# Adafruit_MMA8451.net
KiCad netlist of a schematic drawn in EAGLE
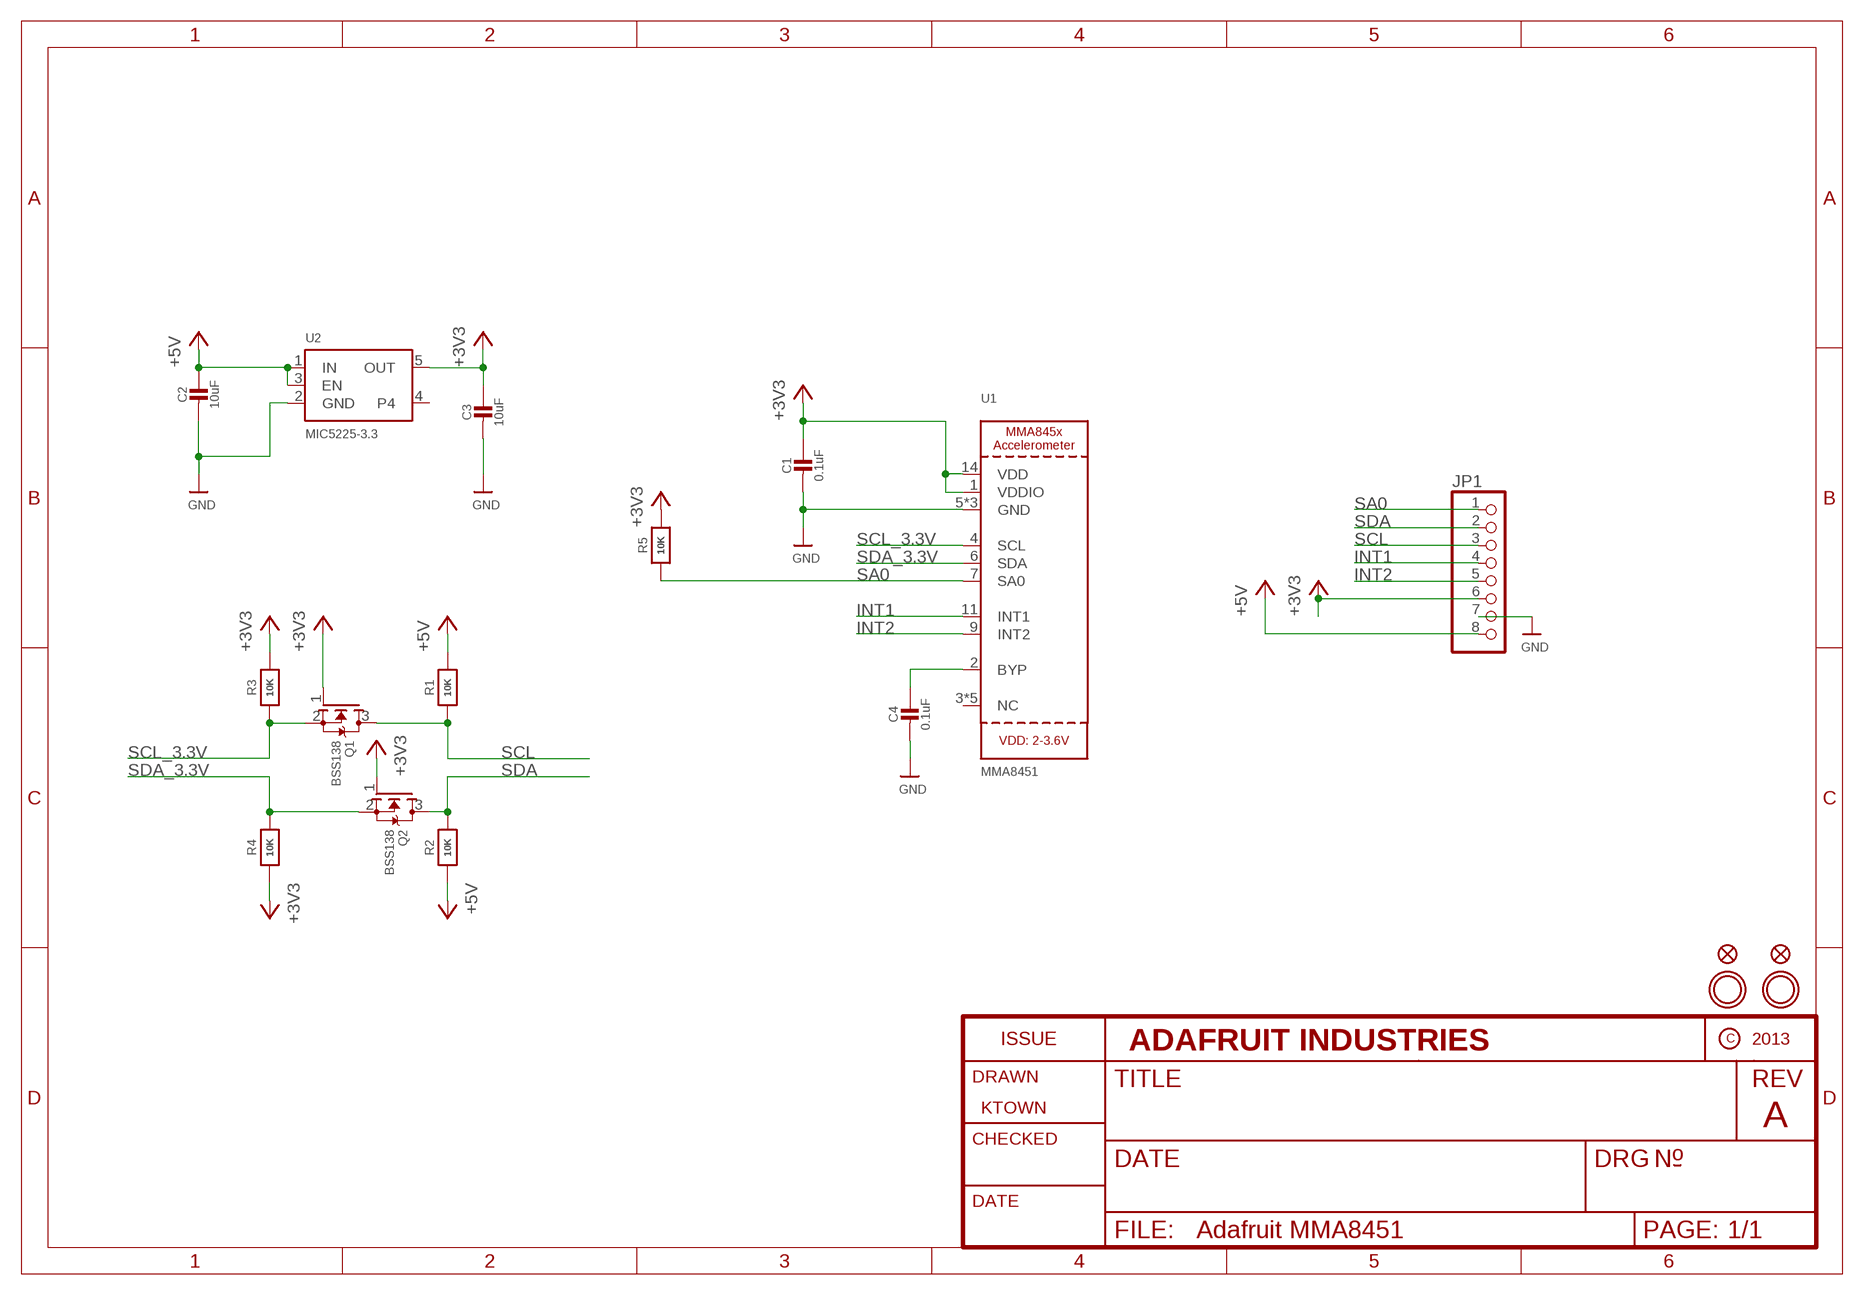
[diagram p0: schematic, sheet 1]

(export (version "E")
  (design (tool "Eeschema 10.0.6"))
  (components
    (comp (ref "C1")
      (value "0.1uF")
      (footprint "eagle-import:0805-NO")
      (libsource (lib "eagle-import") (part "CAP_CERAMIC0805-NOOUTLINE"))
    )
    (comp (ref "C2")
      (value "10uF")
      (footprint "eagle-import:0805-NO")
      (libsource (lib "eagle-import") (part "CAP_CERAMIC0805-NOOUTLINE"))
    )
    (comp (ref "C3")
      (value "10uF")
      (footprint "eagle-import:0805-NO")
      (libsource (lib "eagle-import") (part "CAP_CERAMIC0805-NOOUTLINE"))
    )
    (comp (ref "C4")
      (value "0.1uF")
      (footprint "eagle-import:0805_10MGAP")
      (libsource (lib "eagle-import") (part "CAP_CERAMIC0805_10MGAP"))
    )
    (comp (ref "FID1")
      (value "FIDUCIAL\"\"")
      (footprint "eagle-import:FIDUCIAL_1MM")
      (libsource (lib "eagle-import") (part "FIDUCIAL{dblquote}{dblquote}"))
    )
    (comp (ref "FID2")
      (value "FIDUCIAL\"\"")
      (footprint "eagle-import:FIDUCIAL_1MM")
      (libsource (lib "eagle-import") (part "FIDUCIAL{dblquote}{dblquote}"))
    )
    (comp (ref "JP1")
      (value "HEADER-1X870MIL")
      (footprint "eagle-import:1X08_ROUND_70")
      (libsource (lib "eagle-import") (part "HEADER-1X870MIL"))
    )
    (comp (ref "Q1")
      (value "BSS138")
      (footprint "eagle-import:SOT23-WIDE")
      (libsource (lib "eagle-import") (part "MOSFET-NWIDE"))
    )
    (comp (ref "Q2")
      (value "BSS138")
      (footprint "eagle-import:SOT23-WIDE")
      (libsource (lib "eagle-import") (part "MOSFET-NWIDE"))
    )
    (comp (ref "R1")
      (value "10K")
      (footprint "eagle-import:0805-NO")
      (libsource (lib "eagle-import") (part "RESISTOR0805_NOOUTLINE"))
    )
    (comp (ref "R2")
      (value "10K")
      (footprint "eagle-import:0805-NO")
      (libsource (lib "eagle-import") (part "RESISTOR0805_NOOUTLINE"))
    )
    (comp (ref "R3")
      (value "10K")
      (footprint "eagle-import:0805-NO")
      (libsource (lib "eagle-import") (part "RESISTOR0805_NOOUTLINE"))
    )
    (comp (ref "R4")
      (value "10K")
      (footprint "eagle-import:0805-NO")
      (libsource (lib "eagle-import") (part "RESISTOR0805_NOOUTLINE"))
    )
    (comp (ref "R5")
      (value "10K")
      (footprint "eagle-import:0805-NO")
      (libsource (lib "eagle-import") (part "RESISTOR0805_NOOUTLINE"))
    )
    (comp (ref "U$3")
      (value "MOUNTINGHOLE2.5")
      (footprint "eagle-import:MOUNTINGHOLE_2.5_PLATED")
      (libsource (lib "eagle-import") (part "MOUNTINGHOLE2.5"))
    )
    (comp (ref "U$6")
      (value "MOUNTINGHOLE2.5")
      (footprint "eagle-import:MOUNTINGHOLE_2.5_PLATED")
      (libsource (lib "eagle-import") (part "MOUNTINGHOLE2.5"))
    )
    (comp (ref "U1")
      (value "MMA8451")
      (footprint "eagle-import:MMA845X_QFN_16MM")
      (libsource (lib "eagle-import") (part "ACCEL_MMA845X"))
    )
    (comp (ref "U2")
      (value "MIC5225-3.3")
      (footprint "eagle-import:SOT23-5")
      (libsource (lib "eagle-import") (part "VREG_SOT23-5"))
    )
  )
  (nets
    (net (code "1") (name "+3V3") (class "Default")
      (node (ref "C1") (pin "1") (pinfunction "1_1") (pintype "passive"))
      (node (ref "C3") (pin "1") (pinfunction "1_1") (pintype "passive"))
      (node (ref "JP1") (pin "6") (pinfunction "6_6") (pintype "passive"))
      (node (ref "Q1") (pin "1") (pinfunction "G_1") (pintype "bidirectional"))
      (node (ref "Q2") (pin "1") (pinfunction "G_1") (pintype "bidirectional"))
      (node (ref "R3") (pin "2") (pinfunction "2_2") (pintype "passive"))
      (node (ref "R4") (pin "1") (pinfunction "1_1") (pintype "passive"))
      (node (ref "R5") (pin "2") (pinfunction "2_2") (pintype "passive"))
      (node (ref "U1") (pin "1") (pinfunction "VDDIO_1") (pintype "power_in"))
      (node (ref "U1") (pin "14") (pinfunction "VDD_14") (pintype "power_in"))
      (node (ref "U2") (pin "5") (pinfunction "OUT_5") (pintype "power_in"))
    )
    (net (code "2") (name "+5V") (class "Default")
      (node (ref "C2") (pin "1") (pinfunction "1_1") (pintype "passive"))
      (node (ref "JP1") (pin "8") (pinfunction "8_8") (pintype "passive"))
      (node (ref "R1") (pin "2") (pinfunction "2_2") (pintype "passive"))
      (node (ref "R2") (pin "1") (pinfunction "1_1") (pintype "passive"))
      (node (ref "U2") (pin "1") (pinfunction "IN_1") (pintype "power_in"))
      (node (ref "U2") (pin "3") (pinfunction "EN_3") (pintype "input"))
    )
    (net (code "3") (name "/INT1") (class "Default")
      (node (ref "JP1") (pin "4") (pinfunction "4_4") (pintype "passive"))
      (node (ref "U1") (pin "11") (pinfunction "INT1_11") (pintype "output"))
    )
    (net (code "4") (name "/INT2") (class "Default")
      (node (ref "JP1") (pin "5") (pinfunction "5_5") (pintype "passive"))
      (node (ref "U1") (pin "9") (pinfunction "INT2_9") (pintype "output"))
    )
    (net (code "5") (name "/SA0") (class "Default")
      (node (ref "JP1") (pin "1") (pinfunction "1_1") (pintype "passive"))
      (node (ref "R5") (pin "1") (pinfunction "1_1") (pintype "passive"))
      (node (ref "U1") (pin "7") (pinfunction "SA0_7") (pintype "input"))
    )
    (net (code "6") (name "/SCL") (class "Default")
      (node (ref "JP1") (pin "3") (pinfunction "3_3") (pintype "passive"))
      (node (ref "Q1") (pin "3") (pinfunction "D_3") (pintype "bidirectional"))
      (node (ref "R1") (pin "1") (pinfunction "1_1") (pintype "passive"))
    )
    (net (code "7") (name "/SCL_3.3V") (class "Default")
      (node (ref "Q1") (pin "2") (pinfunction "S_2") (pintype "bidirectional"))
      (node (ref "R3") (pin "1") (pinfunction "1_1") (pintype "passive"))
      (node (ref "U1") (pin "4") (pinfunction "SCL_4") (pintype "open_collector"))
    )
    (net (code "8") (name "/SDA") (class "Default")
      (node (ref "JP1") (pin "2") (pinfunction "2_2") (pintype "passive"))
      (node (ref "Q2") (pin "3") (pinfunction "D_3") (pintype "bidirectional"))
      (node (ref "R2") (pin "2") (pinfunction "2_2") (pintype "passive"))
    )
    (net (code "9") (name "/SDA_3.3V") (class "Default")
      (node (ref "Q2") (pin "2") (pinfunction "S_2") (pintype "bidirectional"))
      (node (ref "R4") (pin "2") (pinfunction "2_2") (pintype "passive"))
      (node (ref "U1") (pin "6") (pinfunction "SDA_6") (pintype "open_collector"))
    )
    (net (code "10") (name "GND") (class "Default")
      (node (ref "C1") (pin "2") (pinfunction "2_2") (pintype "passive"))
      (node (ref "C2") (pin "2") (pinfunction "2_2") (pintype "passive"))
      (node (ref "C3") (pin "2") (pinfunction "2_2") (pintype "passive"))
      (node (ref "C4") (pin "2") (pinfunction "2_2") (pintype "passive"))
      (node (ref "JP1") (pin "7") (pinfunction "7_7") (pintype "passive"))
      (node (ref "U1") (pin "10") (pinfunction "GND_10") (pintype "power_in"))
      (node (ref "U1") (pin "12") (pinfunction "GND_12") (pintype "power_in"))
      (node (ref "U1") (pin "5") (pinfunction "GND_5") (pintype "power_in"))
      (node (ref "U2") (pin "2") (pinfunction "GND_2") (pintype "power_in"))
    )
    (net (code "11") (name "Net-(U1-BYP)") (class "Default")
      (node (ref "C4") (pin "1") (pinfunction "1_1") (pintype "passive"))
      (node (ref "U1") (pin "2") (pinfunction "BYP_2") (pintype "input"))
    )
    (net (code "12") (name "unconnected-(U1-NC-Pad3)") (class "Default")
      (node (ref "U1") (pin "3") (pinfunction "NC_3") (pintype "no_connect"))
    )
    (net (code "13") (name "unconnected-(U1-NC-Pad8)") (class "Default")
      (node (ref "U1") (pin "8") (pinfunction "NC_8") (pintype "no_connect"))
    )
    (net (code "14") (name "unconnected-(U1-NC-Pad13)") (class "Default")
      (node (ref "U1") (pin "13") (pinfunction "NC_13") (pintype "no_connect"))
    )
    (net (code "15") (name "unconnected-(U1-NC-Pad15)") (class "Default")
      (node (ref "U1") (pin "15") (pinfunction "NC_15") (pintype "no_connect"))
    )
    (net (code "16") (name "unconnected-(U1-NC-Pad16)") (class "Default")
      (node (ref "U1") (pin "16") (pinfunction "NC_16") (pintype "no_connect"))
    )
    (net (code "17") (name "unconnected-(U2-P4-Pad4)") (class "Default")
      (node (ref "U2") (pin "4") (pinfunction "P4_4") (pintype "bidirectional"))
    )
  )
)
